# Control_core.net
KiCad netlist of a schematic drawn in Altium Designer
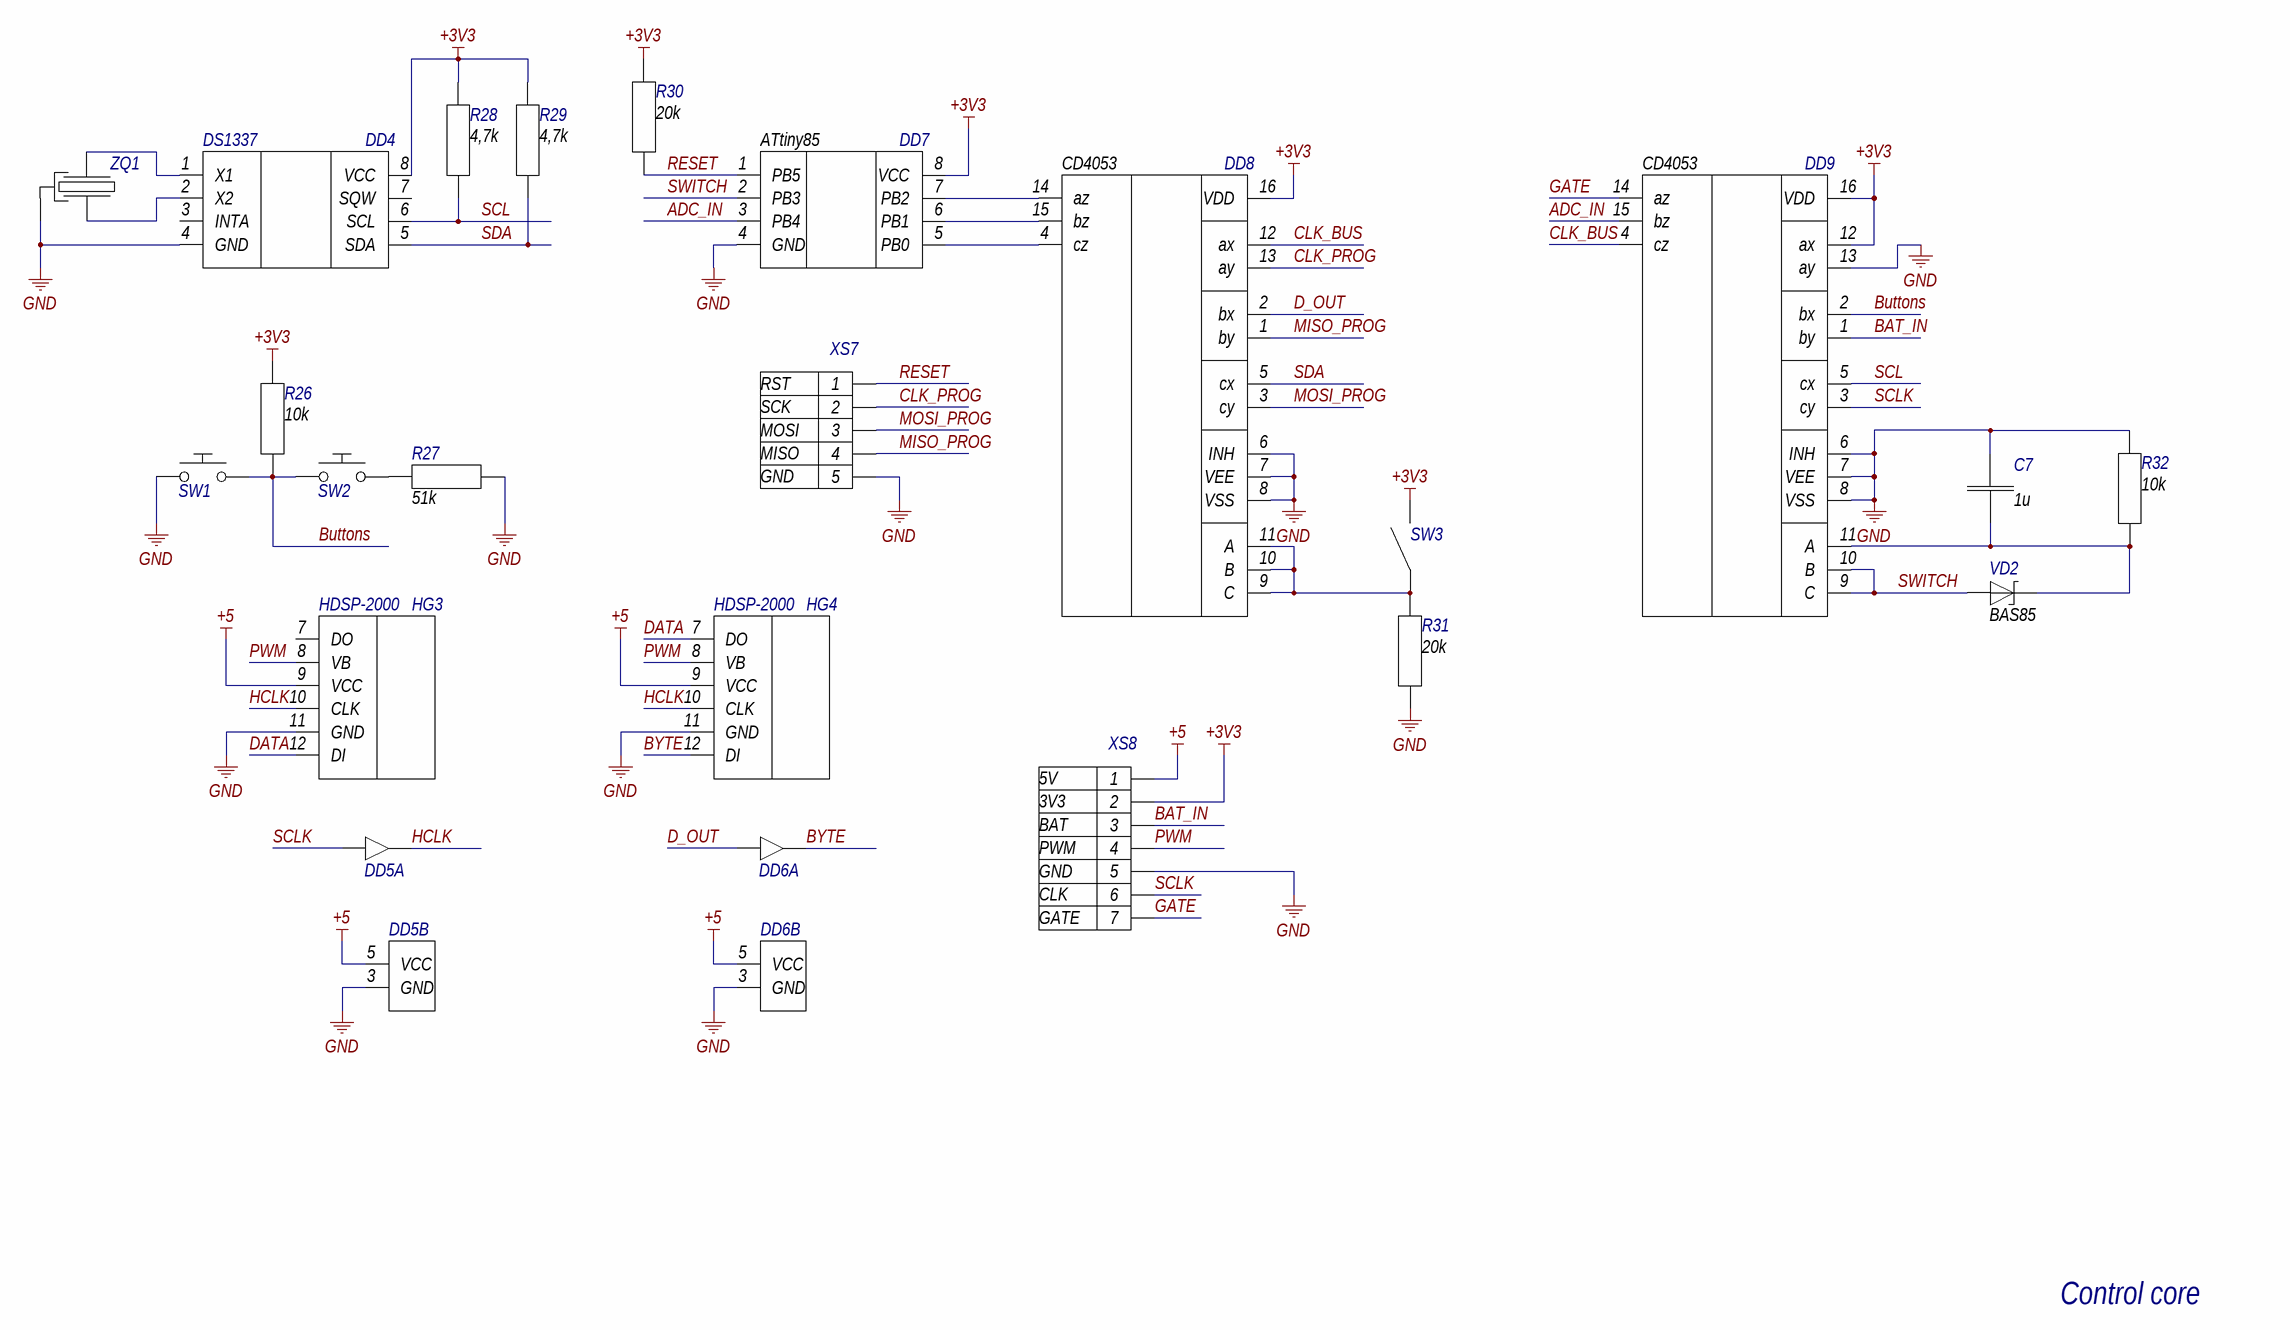
[diagram p0: Control_core.SchDoc]

(export (version "E")
  (design (tool "Eeschema 10.0.6"))
  (components
    (comp (ref "C7")
      (value "1u")
      (footprint "CHIP-0805")
      (fields (field (name "Comment") "C0805"))
      (libsource (lib "Schlib1") (part "C0805"))
    )
    (comp (ref "DD4")
      (value "DS1337")
      (footprint "SOIC-8")
      (fields (field (name "NAME") "DS1337") (field (name "MANUFACTURER") "Maxim"))
      (libsource (lib "Schlib1") (part "DS1337"))
    )
    (comp (ref "DD5") (value "74LV1T34") (footprint "SOT23-5") (libsource (lib "Schlib1") (part "74LV1T34")))
    (comp (ref "DD6") (value "74LV1T34") (footprint "SOT23-5") (libsource (lib "Schlib1") (part "74LV1T34")))
    (comp (ref "DD7")
      (value "ATtiny85")
      (footprint "SOIC-8-ATtiny85")
      (fields (field (name "NAME") "ATtiny85"))
      (libsource (lib "Schlib1") (part "ATtiny85"))
    )
    (comp (ref "DD8")
      (value "CD4053")
      (footprint "SOIC-16")
      (fields (field (name "NAME") "CD4053"))
      (libsource (lib "Schlib1") (part "CD4053"))
    )
    (comp (ref "DD9")
      (value "CD4053")
      (footprint "SOIC-16")
      (fields (field (name "NAME") "CD4053"))
      (libsource (lib "Schlib1") (part "CD4053"))
    )
    (comp (ref "HG3")
      (value "HDSP-2000_SPI")
      (footprint "HDSP-2000_SPI")
      (fields (field (name "MANUFACTURER") "HP") (field (name "NAME") "HDSP-2000"))
      (libsource (lib "Schlib1") (part "HDSP-2000_SPI"))
    )
    (comp (ref "HG4")
      (value "HDSP-2000_SPI")
      (footprint "HDSP-2000_SPI")
      (fields (field (name "MANUFACTURER") "HP") (field (name "NAME") "HDSP-2000"))
      (libsource (lib "Schlib1") (part "HDSP-2000_SPI"))
    )
    (comp (ref "R26")
      (value "10k")
      (footprint "CHIP-0402")
      (fields (field (name "Comment") "R0402"))
      (libsource (lib "") (part "R0402_1"))
    )
    (comp (ref "R27")
      (value "51k")
      (footprint "CHIP-0402")
      (fields (field (name "Comment") "R0402"))
      (libsource (lib "Schlib1") (part "R0402"))
    )
    (comp (ref "R28")
      (value "4,7k")
      (footprint "CHIP-0402")
      (fields (field (name "Comment") "R0402"))
      (libsource (lib "") (part "R0402_1"))
    )
    (comp (ref "R29")
      (value "4,7k")
      (footprint "CHIP-0402")
      (fields (field (name "Comment") "R0402"))
      (libsource (lib "") (part "R0402_1"))
    )
    (comp (ref "R30")
      (value "20k")
      (footprint "CHIP-0402")
      (fields (field (name "Comment") "R0402"))
      (libsource (lib "") (part "R0402_1"))
    )
    (comp (ref "R31")
      (value "20k")
      (footprint "CHIP-0402")
      (fields (field (name "Comment") "R0402"))
      (libsource (lib "") (part "R0402_2"))
    )
    (comp (ref "R32")
      (value "10k")
      (footprint "CHIP-0402")
      (fields (field (name "Comment") "R0402"))
      (libsource (lib "") (part "R0402_1"))
    )
    (comp (ref "SW1") (value "Button") (footprint "BUTTON") (libsource (lib "Schlib1") (part "Button")))
    (comp (ref "SW2") (value "Button") (footprint "BUTTON") (libsource (lib "Schlib1") (part "Button")))
    (comp (ref "SW3") (value "Switch") (footprint "SWITCH") (libsource (lib "Schlib1") (part "Switch")))
    (comp (ref "VD2")
      (value "BAS85")
      (footprint "DIOD_MELF")
      (fields (field (name "NAME") "BAS85"))
      (libsource (lib "Schlib1") (part "BAS85"))
    )
    (comp (ref "XS7")
      (value "Prog_connector")
      (footprint "Prog_connector")
      (libsource (lib "Schlib1") (part "Prog_connector"))
    )
    (comp (ref "XS8")
      (value "Socket_7")
      (footprint "SOCKET_7")
      (fields
        (field (name "PIN7") "GATE")
        (field (name "PIN6") "CLK")
        (field (name "PIN5") "GND")
        (field (name "PIN4") "PWM")
        (field (name "PIN3") "BAT")
        (field (name "PIN2") "3V3")
        (field (name "PIN1") "5V")
      )
      (libsource (lib "Schlib1") (part "Socket_7"))
    )
    (comp (ref "ZQ1") (value "HZ") (footprint "HZ") (libsource (lib "Schlib1") (part "HZ")))
  )
  (nets
    (net (code "1") (name "+3V3") (class "Default")
      (node (ref "DD4") (pin "8") (pinfunction "VCC_8") (pintype "passive"))
      (node (ref "DD7") (pin "8") (pinfunction "VCC_8") (pintype "passive"))
      (node (ref "DD8") (pin "16") (pinfunction "VDD_16") (pintype "passive"))
      (node (ref "DD9") (pin "12") (pinfunction "ax_12") (pintype "passive"))
      (node (ref "DD9") (pin "16") (pinfunction "VDD_16") (pintype "passive"))
      (node (ref "R26") (pin "2") (pinfunction "2_2") (pintype "passive"))
      (node (ref "R28") (pin "2") (pinfunction "2_2") (pintype "passive"))
      (node (ref "R29") (pin "2") (pinfunction "2_2") (pintype "passive"))
      (node (ref "R30") (pin "2") (pinfunction "2_2") (pintype "passive"))
      (node (ref "SW3") (pin "2") (pinfunction "2_2") (pintype "passive"))
      (node (ref "XS8") (pin "2") (pinfunction "2_2") (pintype "passive"))
    )
    (net (code "2") (name "+5") (class "Default")
      (node (ref "DD5") (pin "5") (pinfunction "VCC_5") (pintype "passive"))
      (node (ref "DD6") (pin "5") (pinfunction "VCC_5") (pintype "passive"))
      (node (ref "HG3") (pin "9") (pinfunction "VCC_9") (pintype "passive"))
      (node (ref "HG4") (pin "9") (pinfunction "VCC_9") (pintype "passive"))
      (node (ref "XS8") (pin "1") (pinfunction "1_1") (pintype "passive"))
    )
    (net (code "3") (name "/ADC_IN") (class "Default")
      (node (ref "DD7") (pin "3") (pinfunction "PB4_3") (pintype "passive"))
      (node (ref "DD9") (pin "15") (pinfunction "bz_15") (pintype "passive"))
    )
    (net (code "4") (name "/BAT_IN") (class "Default")
      (node (ref "DD9") (pin "1") (pinfunction "by_1") (pintype "passive"))
      (node (ref "XS8") (pin "3") (pinfunction "3_3") (pintype "passive"))
    )
    (net (code "5") (name "/BYTE") (class "Default")
      (node (ref "DD6") (pin "4") (pinfunction "OUT_4") (pintype "passive"))
      (node (ref "HG4") (pin "12") (pinfunction "DI_12") (pintype "passive"))
    )
    (net (code "6") (name "/Buttons") (class "Default")
      (node (ref "DD9") (pin "2") (pinfunction "bx_2") (pintype "passive"))
      (node (ref "R26") (pin "1") (pinfunction "1_1") (pintype "passive"))
      (node (ref "SW1") (pin "2") (pinfunction "2_2") (pintype "passive"))
      (node (ref "SW2") (pin "1") (pinfunction "1_1") (pintype "passive"))
    )
    (net (code "7") (name "/CLK_BUS") (class "Default")
      (node (ref "DD8") (pin "12") (pinfunction "ax_12") (pintype "passive"))
      (node (ref "DD9") (pin "4") (pinfunction "cz_4") (pintype "passive"))
    )
    (net (code "8") (name "/CLK_PROG") (class "Default")
      (node (ref "DD8") (pin "13") (pinfunction "ay_13") (pintype "passive"))
      (node (ref "XS7") (pin "2") (pinfunction "2_2") (pintype "passive"))
    )
    (net (code "9") (name "/DATA") (class "Default")
      (node (ref "HG3") (pin "12") (pinfunction "DI_12") (pintype "passive"))
      (node (ref "HG4") (pin "7") (pinfunction "DO_7") (pintype "passive"))
    )
    (net (code "10") (name "/D_OUT") (class "Default")
      (node (ref "DD6") (pin "2") (pinfunction "IN_2") (pintype "passive"))
      (node (ref "DD8") (pin "2") (pinfunction "bx_2") (pintype "passive"))
    )
    (net (code "11") (name "/GATE") (class "Default")
      (node (ref "DD9") (pin "14") (pinfunction "az_14") (pintype "passive"))
      (node (ref "XS8") (pin "7") (pinfunction "7_7") (pintype "passive"))
    )
    (net (code "12") (name "/HCLK") (class "Default")
      (node (ref "DD5") (pin "4") (pinfunction "OUT_4") (pintype "passive"))
      (node (ref "HG3") (pin "10") (pinfunction "CLK_10") (pintype "passive"))
      (node (ref "HG4") (pin "10") (pinfunction "CLK_10") (pintype "passive"))
    )
    (net (code "13") (name "/MISO_PROG") (class "Default")
      (node (ref "DD8") (pin "1") (pinfunction "by_1") (pintype "passive"))
      (node (ref "XS7") (pin "4") (pinfunction "4_4") (pintype "passive"))
    )
    (net (code "14") (name "/MOSI_PROG") (class "Default")
      (node (ref "DD8") (pin "3") (pinfunction "cy_3") (pintype "passive"))
      (node (ref "XS7") (pin "3") (pinfunction "3_3") (pintype "passive"))
    )
    (net (code "15") (name "/PWM") (class "Default")
      (node (ref "HG3") (pin "8") (pinfunction "VB_8") (pintype "passive"))
      (node (ref "HG4") (pin "8") (pinfunction "VB_8") (pintype "passive"))
      (node (ref "XS8") (pin "4") (pinfunction "4_4") (pintype "passive"))
    )
    (net (code "16") (name "/RESET") (class "Default")
      (node (ref "DD7") (pin "1") (pinfunction "PB5_1") (pintype "passive"))
      (node (ref "R30") (pin "1") (pinfunction "1_1") (pintype "passive"))
      (node (ref "XS7") (pin "1") (pinfunction "1_1") (pintype "passive"))
    )
    (net (code "17") (name "/SCL") (class "Default")
      (node (ref "DD4") (pin "6") (pinfunction "SCL_6") (pintype "passive"))
      (node (ref "DD9") (pin "5") (pinfunction "cx_5") (pintype "passive"))
      (node (ref "R28") (pin "1") (pinfunction "1_1") (pintype "passive"))
    )
    (net (code "18") (name "/SCLK") (class "Default")
      (node (ref "DD5") (pin "2") (pinfunction "IN_2") (pintype "passive"))
      (node (ref "DD9") (pin "3") (pinfunction "cy_3") (pintype "passive"))
      (node (ref "XS8") (pin "6") (pinfunction "6_6") (pintype "passive"))
    )
    (net (code "19") (name "/SDA") (class "Default")
      (node (ref "DD4") (pin "5") (pinfunction "SDA_5") (pintype "passive"))
      (node (ref "DD8") (pin "5") (pinfunction "cx_5") (pintype "passive"))
      (node (ref "R29") (pin "1") (pinfunction "1_1") (pintype "passive"))
    )
    (net (code "20") (name "/SWITCH") (class "Default")
      (node (ref "DD7") (pin "2") (pinfunction "PB3_2") (pintype "passive"))
      (node (ref "DD9") (pin "10") (pinfunction "B_10") (pintype "passive"))
      (node (ref "DD9") (pin "9") (pinfunction "C_9") (pintype "passive"))
      (node (ref "VD2") (pin "2") (pinfunction "A_2") (pintype "passive"))
    )
    (net (code "21") (name "GND") (class "Default")
      (node (ref "C7") (pin "2") (pinfunction "2_2") (pintype "passive"))
      (node (ref "DD4") (pin "4") (pinfunction "GND_4") (pintype "passive"))
      (node (ref "DD5") (pin "3") (pinfunction "GND_3") (pintype "passive"))
      (node (ref "DD6") (pin "3") (pinfunction "GND_3") (pintype "passive"))
      (node (ref "DD7") (pin "4") (pinfunction "GND_4") (pintype "passive"))
      (node (ref "DD8") (pin "6") (pinfunction "INH_6") (pintype "passive"))
      (node (ref "DD8") (pin "7") (pinfunction "VEE_7") (pintype "passive"))
      (node (ref "DD8") (pin "8") (pinfunction "VSS_8") (pintype "passive"))
      (node (ref "DD9") (pin "13") (pinfunction "ay_13") (pintype "passive"))
      (node (ref "DD9") (pin "6") (pinfunction "INH_6") (pintype "passive"))
      (node (ref "DD9") (pin "7") (pinfunction "VEE_7") (pintype "passive"))
      (node (ref "DD9") (pin "8") (pinfunction "VSS_8") (pintype "passive"))
      (node (ref "HG3") (pin "11") (pinfunction "GND_11") (pintype "passive"))
      (node (ref "HG4") (pin "11") (pinfunction "GND_11") (pintype "passive"))
      (node (ref "R27") (pin "2") (pinfunction "2_2") (pintype "passive"))
      (node (ref "R31") (pin "2") (pinfunction "2_2") (pintype "passive"))
      (node (ref "R32") (pin "2") (pinfunction "2_2") (pintype "passive"))
      (node (ref "SW1") (pin "1") (pinfunction "1_1") (pintype "passive"))
      (node (ref "XS7") (pin "5") (pinfunction "5_5") (pintype "passive"))
      (node (ref "XS8") (pin "5") (pinfunction "5_5") (pintype "passive"))
      (node (ref "ZQ1") (pin "3") (pinfunction "3_3") (pintype "passive"))
    )
    (net (code "22") (name "Net-(DD4-X1)") (class "Default")
      (node (ref "DD4") (pin "1") (pinfunction "X1_1") (pintype "passive"))
      (node (ref "ZQ1") (pin "1") (pinfunction "1_1") (pintype "passive"))
    )
    (net (code "23") (name "Net-(DD4-X2)") (class "Default")
      (node (ref "DD4") (pin "2") (pinfunction "X2_2") (pintype "passive"))
      (node (ref "ZQ1") (pin "2") (pinfunction "2_2") (pintype "passive"))
    )
    (net (code "24") (name "Net-(DD7-PB0)") (class "Default")
      (node (ref "DD7") (pin "5") (pinfunction "PB0_5") (pintype "passive"))
      (node (ref "DD8") (pin "4") (pinfunction "cz_4") (pintype "passive"))
    )
    (net (code "25") (name "Net-(DD7-PB1)") (class "Default")
      (node (ref "DD7") (pin "6") (pinfunction "PB1_6") (pintype "passive"))
      (node (ref "DD8") (pin "15") (pinfunction "bz_15") (pintype "passive"))
    )
    (net (code "26") (name "Net-(DD7-PB2)") (class "Default")
      (node (ref "DD7") (pin "7") (pinfunction "PB2_7") (pintype "passive"))
      (node (ref "DD8") (pin "14") (pinfunction "az_14") (pintype "passive"))
    )
    (net (code "27") (name "Net-(DD8-A)") (class "Default")
      (node (ref "DD8") (pin "10") (pinfunction "B_10") (pintype "passive"))
      (node (ref "DD8") (pin "11") (pinfunction "A_11") (pintype "passive"))
      (node (ref "DD8") (pin "9") (pinfunction "C_9") (pintype "passive"))
      (node (ref "R31") (pin "1") (pinfunction "1_1") (pintype "passive"))
      (node (ref "SW3") (pin "1") (pinfunction "1_1") (pintype "passive"))
    )
    (net (code "28") (name "Net-(DD9-A)") (class "Default")
      (node (ref "C7") (pin "1") (pinfunction "1_1") (pintype "passive"))
      (node (ref "DD9") (pin "11") (pinfunction "A_11") (pintype "passive"))
      (node (ref "R32") (pin "1") (pinfunction "1_1") (pintype "passive"))
      (node (ref "VD2") (pin "1") (pinfunction "K_1") (pintype "passive"))
    )
    (net (code "29") (name "Net-(R27-Pad1)") (class "Default")
      (node (ref "R27") (pin "1") (pinfunction "1_1") (pintype "passive"))
      (node (ref "SW2") (pin "2") (pinfunction "2_2") (pintype "passive"))
    )
    (net (code "30") (name "unconnected-(DD4-INTA-Pad3)") (class "Default")
      (node (ref "DD4") (pin "3") (pinfunction "INTA_3") (pintype "passive"))
    )
    (net (code "31") (name "unconnected-(DD4-SQW-Pad7)") (class "Default")
      (node (ref "DD4") (pin "7") (pinfunction "SQW_7") (pintype "passive"))
    )
    (net (code "32") (name "unconnected-(HG3-DO-Pad7)") (class "Default")
      (node (ref "HG3") (pin "7") (pinfunction "DO_7") (pintype "passive"))
    )
  )
)
